# Sensors_TestBoard.net
KiCad netlist of a schematic drawn in Altium Designer
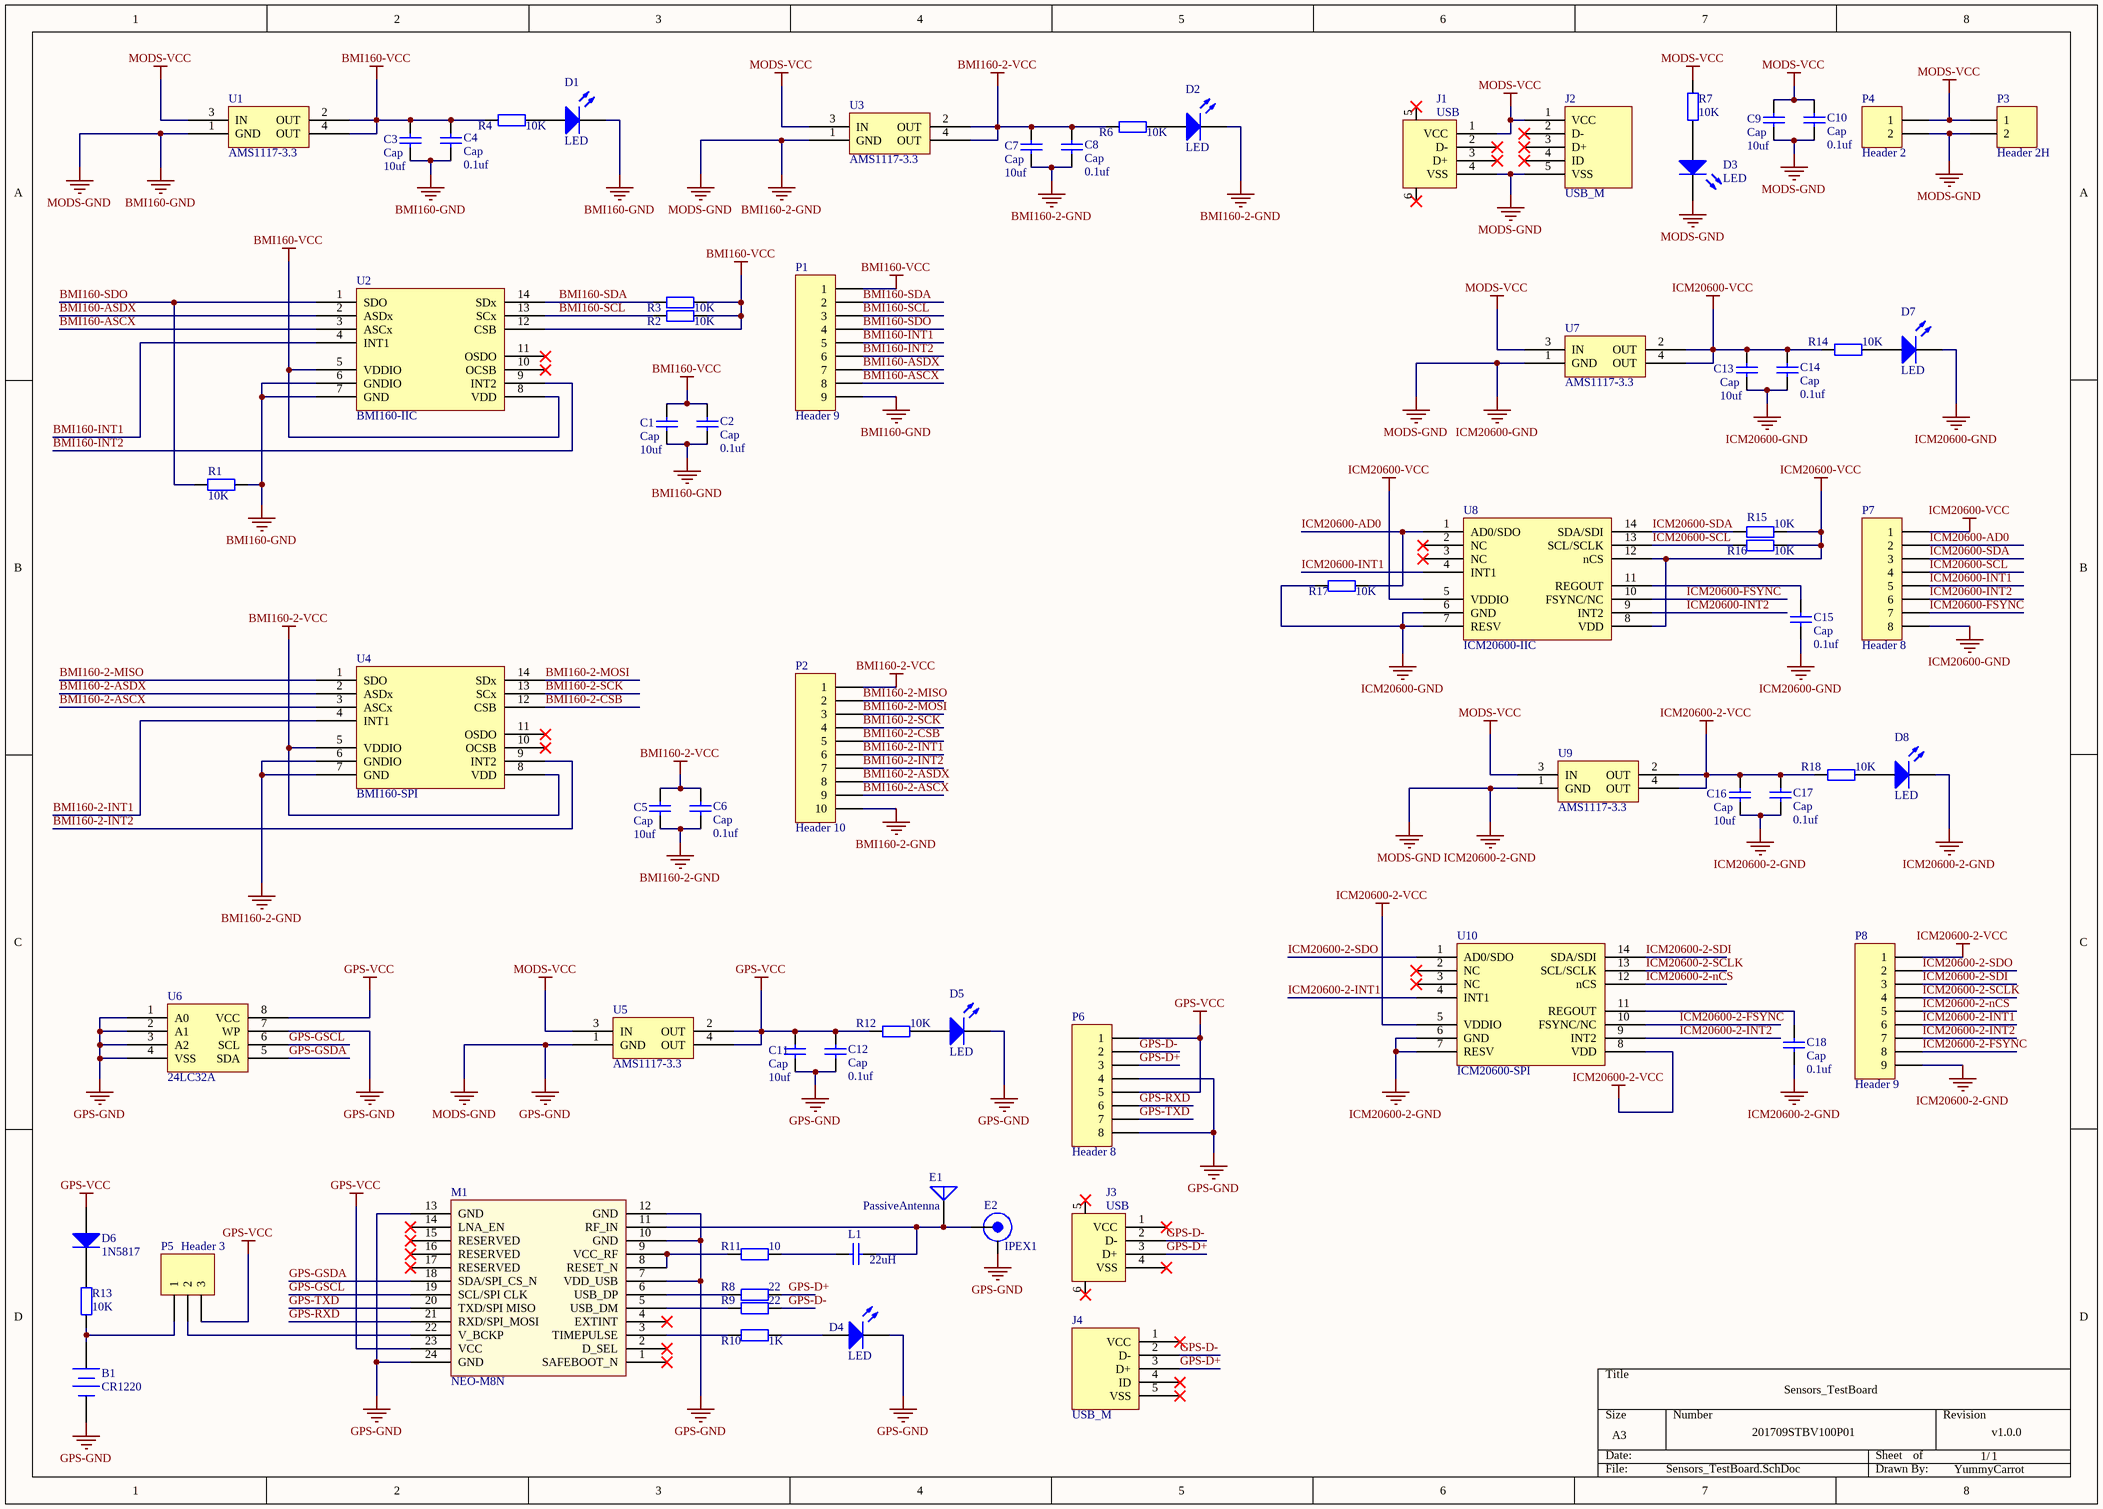
[diagram p0: Sensors_TestBoard.SchDoc]

(export (version "E")
  (design (tool "Eeschema 10.0.6"))
  (components
    (comp (ref "B1") (value "CR1220") (footprint "CR1220") (libsource (lib "Basic_lib") (part "CR1220")))
    (comp (ref "C1")
      (value "Cap")
      (footprint "C1206")
      (fields (field (name "ALTIUM_VALUE") "10uf"))
      (libsource (lib "Basic_lib") (part "Cap"))
    )
    (comp (ref "C2")
      (value "Cap")
      (footprint "C1206")
      (fields (field (name "ALTIUM_VALUE") "0.1uf"))
      (libsource (lib "Basic_lib") (part "Cap"))
    )
    (comp (ref "C3")
      (value "Cap")
      (footprint "C1206")
      (fields (field (name "ALTIUM_VALUE") "10uf"))
      (libsource (lib "Basic_lib") (part "Cap"))
    )
    (comp (ref "C4")
      (value "Cap")
      (footprint "C1206")
      (fields (field (name "ALTIUM_VALUE") "0.1uf"))
      (libsource (lib "Basic_lib") (part "Cap"))
    )
    (comp (ref "C5")
      (value "Cap")
      (footprint "C1206")
      (fields (field (name "ALTIUM_VALUE") "10uf"))
      (libsource (lib "Basic_lib") (part "Cap"))
    )
    (comp (ref "C6")
      (value "Cap")
      (footprint "C1206")
      (fields (field (name "ALTIUM_VALUE") "0.1uf"))
      (libsource (lib "Basic_lib") (part "Cap"))
    )
    (comp (ref "C7")
      (value "Cap")
      (footprint "C1206")
      (fields (field (name "ALTIUM_VALUE") "10uf"))
      (libsource (lib "Basic_lib") (part "Cap"))
    )
    (comp (ref "C8")
      (value "Cap")
      (footprint "C1206")
      (fields (field (name "ALTIUM_VALUE") "0.1uf"))
      (libsource (lib "Basic_lib") (part "Cap"))
    )
    (comp (ref "C9")
      (value "Cap")
      (footprint "C1206")
      (fields (field (name "ALTIUM_VALUE") "10uf"))
      (libsource (lib "Basic_lib") (part "Cap"))
    )
    (comp (ref "C10")
      (value "Cap")
      (footprint "C1206")
      (fields (field (name "ALTIUM_VALUE") "0.1uf"))
      (libsource (lib "Basic_lib") (part "Cap"))
    )
    (comp (ref "C11")
      (value "Cap")
      (footprint "C1206")
      (fields (field (name "ALTIUM_VALUE") "10uf"))
      (libsource (lib "Basic_lib") (part "Cap"))
    )
    (comp (ref "C12")
      (value "Cap")
      (footprint "C1206")
      (fields (field (name "ALTIUM_VALUE") "0.1uf"))
      (libsource (lib "Basic_lib") (part "Cap"))
    )
    (comp (ref "C13")
      (value "Cap")
      (footprint "C1206")
      (fields (field (name "ALTIUM_VALUE") "10uf"))
      (libsource (lib "Basic_lib") (part "Cap"))
    )
    (comp (ref "C14")
      (value "Cap")
      (footprint "C1206")
      (fields (field (name "ALTIUM_VALUE") "0.1uf"))
      (libsource (lib "Basic_lib") (part "Cap"))
    )
    (comp (ref "C15")
      (value "Cap")
      (footprint "C1206")
      (fields (field (name "ALTIUM_VALUE") "0.1uf"))
      (libsource (lib "Basic_lib") (part "Cap"))
    )
    (comp (ref "C16")
      (value "Cap")
      (footprint "C1206")
      (fields (field (name "ALTIUM_VALUE") "10uf"))
      (libsource (lib "Basic_lib") (part "Cap"))
    )
    (comp (ref "C17")
      (value "Cap")
      (footprint "C1206")
      (fields (field (name "ALTIUM_VALUE") "0.1uf"))
      (libsource (lib "Basic_lib") (part "Cap"))
    )
    (comp (ref "C18")
      (value "Cap")
      (footprint "C1206")
      (fields (field (name "ALTIUM_VALUE") "0.1uf"))
      (libsource (lib "Basic_lib") (part "Cap"))
    )
    (comp (ref "D1")
      (value "LED")
      (footprint "3.2X1.6X1.1")
      (description "Typical RED, GREEN, YELLOW, AMBER GaAs LED")
      (fields (field (name "PUBLISHER") "Altium Limited"))
      (libsource (lib "Miscellaneous Devices") (part "LED2"))
    )
    (comp (ref "D2")
      (value "LED")
      (footprint "3.2X1.6X1.1")
      (description "Typical RED, GREEN, YELLOW, AMBER GaAs LED")
      (fields (field (name "PUBLISHER") "Altium Limited"))
      (libsource (lib "Miscellaneous Devices") (part "LED2"))
    )
    (comp (ref "D3")
      (value "LED")
      (footprint "3.2X1.6X1.1")
      (description "Typical RED, GREEN, YELLOW, AMBER GaAs LED")
      (fields (field (name "PUBLISHER") "Altium Limited"))
      (libsource (lib "Miscellaneous Devices") (part "LED2"))
    )
    (comp (ref "D4")
      (value "LED")
      (footprint "3.2X1.6X1.1")
      (description "Typical RED, GREEN, YELLOW, AMBER GaAs LED")
      (fields (field (name "PUBLISHER") "Altium Limited"))
      (libsource (lib "Miscellaneous Devices") (part "LED2"))
    )
    (comp (ref "D5")
      (value "LED")
      (footprint "3.2X1.6X1.1")
      (description "Typical RED, GREEN, YELLOW, AMBER GaAs LED")
      (fields (field (name "PUBLISHER") "Altium Limited"))
      (libsource (lib "Miscellaneous Devices") (part "LED2"))
    )
    (comp (ref "D6")
      (value "1N5817")
      (footprint "Diode-SMA/DO214AC")
      (libsource (lib "Basic_lib") (part "Diode"))
    )
    (comp (ref "D7")
      (value "LED")
      (footprint "3.2X1.6X1.1")
      (description "Typical RED, GREEN, YELLOW, AMBER GaAs LED")
      (fields (field (name "PUBLISHER") "Altium Limited"))
      (libsource (lib "Miscellaneous Devices") (part "LED2"))
    )
    (comp (ref "D8")
      (value "LED")
      (footprint "3.2X1.6X1.1")
      (description "Typical RED, GREEN, YELLOW, AMBER GaAs LED")
      (fields (field (name "PUBLISHER") "Altium Limited"))
      (libsource (lib "Miscellaneous Devices") (part "LED2"))
    )
    (comp (ref "E1")
      (value "PassiveAntenna")
      (footprint "PassiveAntenna25x25")
      (description "无源天线25x25")
      (libsource (lib "Basic_lib") (part "PassiveAntenna"))
    )
    (comp (ref "E2") (value "IPEX1") (footprint "IPEX1") (libsource (lib "Basic_lib") (part "IPEX1")))
    (comp (ref "J1")
      (value "USB")
      (footprint "USB_A1")
      (description "USB接口")
      (libsource (lib "Fszhanglib") (part "USB"))
    )
    (comp (ref "J2")
      (value "USB_M")
      (footprint "USB_MICRO")
      (description "MicroUSB接口")
      (libsource (lib "Fszhanglib") (part "USB_M"))
    )
    (comp (ref "J3")
      (value "USB")
      (footprint "USB_A1")
      (description "USB接口")
      (libsource (lib "Fszhanglib") (part "USB"))
    )
    (comp (ref "J4")
      (value "USB_M")
      (footprint "USB_MICRO")
      (description "MicroUSB接口")
      (libsource (lib "") (part "USB_M_1"))
    )
    (comp (ref "L1")
      (value "22uH")
      (footprint "C1206")
      (fields (field (name "Comment") "Cap"))
      (libsource (lib "Basic_lib") (part "Cap"))
    )
    (comp (ref "M1") (value "NEO-M8N") (footprint "NEO-M8N") (libsource (lib "Sensors_lib") (part "NEO-M8N")))
    (comp (ref "P1")
      (value "Header 9")
      (footprint "HDR1X9")
      (description "Header, 9-Pin")
      (fields (field (name "PUBLISHER") "Altium Limited"))
      (libsource (lib "Miscellaneous Connectors") (part "Header 9"))
    )
    (comp (ref "P2")
      (value "Header 10")
      (footprint "HDR1X10")
      (description "Header, 10-Pin")
      (fields (field (name "PUBLISHER") "Altium Limited"))
      (libsource (lib "Miscellaneous Connectors") (part "Header 10"))
    )
    (comp (ref "P3")
      (value "Header 2H")
      (footprint "HDR1X2H")
      (description "Header, 2-Pin, Right Angle")
      (fields (field (name "PUBLISHER") "Altium Limited"))
      (libsource (lib "Miscellaneous Connectors") (part "Header 2H"))
    )
    (comp (ref "P4")
      (value "Header 2")
      (footprint "HDR1X2")
      (description "Header, 2-Pin")
      (fields (field (name "PUBLISHER") "Altium Limited"))
      (libsource (lib "Miscellaneous Connectors") (part "Header 2"))
    )
    (comp (ref "P5")
      (value "Header 3")
      (footprint "HDR1X3")
      (description "Header, 3-Pin")
      (fields (field (name "PUBLISHER") "Altium Limited"))
      (libsource (lib "Miscellaneous Connectors") (part "Header 3"))
    )
    (comp (ref "P6")
      (value "Header 8")
      (footprint "HDR1X8")
      (description "Header, 8-Pin")
      (fields (field (name "PUBLISHER") "Altium Limited"))
      (libsource (lib "Miscellaneous Connectors") (part "Header 8"))
    )
    (comp (ref "P7")
      (value "Header 8")
      (footprint "HDR1X8")
      (description "Header, 8-Pin")
      (fields (field (name "PUBLISHER") "Altium Limited"))
      (libsource (lib "Miscellaneous Connectors") (part "Header 8"))
    )
    (comp (ref "P8")
      (value "Header 9")
      (footprint "HDR1X9")
      (description "Header, 9-Pin")
      (fields (field (name "PUBLISHER") "Altium Limited"))
      (libsource (lib "Miscellaneous Connectors") (part "Header 9"))
    )
    (comp (ref "R1")
      (value "10K")
      (footprint "R1206")
      (fields (field (name "Comment") "Res"))
      (libsource (lib "Basic_lib") (part "Res"))
    )
    (comp (ref "R2")
      (value "10K")
      (footprint "R1206")
      (fields (field (name "Comment") "Res"))
      (libsource (lib "Basic_lib") (part "Res"))
    )
    (comp (ref "R3")
      (value "10K")
      (footprint "R1206")
      (fields (field (name "Comment") "Res"))
      (libsource (lib "Basic_lib") (part "Res"))
    )
    (comp (ref "R4")
      (value "10K")
      (footprint "R1206")
      (fields (field (name "Comment") "Res"))
      (libsource (lib "Basic_lib") (part "Res"))
    )
    (comp (ref "R6")
      (value "10K")
      (footprint "R1206")
      (fields (field (name "Comment") "Res"))
      (libsource (lib "Basic_lib") (part "Res"))
    )
    (comp (ref "R7")
      (value "10K")
      (footprint "R1206")
      (fields (field (name "Comment") "Res"))
      (libsource (lib "") (part "Res_1"))
    )
    (comp (ref "R8")
      (value "22")
      (footprint "R1206")
      (fields (field (name "Comment") "Res"))
      (libsource (lib "Basic_lib") (part "Res"))
    )
    (comp (ref "R9")
      (value "22")
      (footprint "R1206")
      (fields (field (name "Comment") "Res"))
      (libsource (lib "Basic_lib") (part "Res"))
    )
    (comp (ref "R10")
      (value "1K")
      (footprint "R1206")
      (fields (field (name "Comment") "Res"))
      (libsource (lib "Basic_lib") (part "Res"))
    )
    (comp (ref "R11")
      (value "10")
      (footprint "R1206")
      (fields (field (name "Comment") "Res"))
      (libsource (lib "Basic_lib") (part "Res"))
    )
    (comp (ref "R12")
      (value "10K")
      (footprint "R1206")
      (fields (field (name "Comment") "Res"))
      (libsource (lib "Basic_lib") (part "Res"))
    )
    (comp (ref "R13")
      (value "10K")
      (footprint "R1206")
      (fields (field (name "Comment") "Res"))
      (libsource (lib "") (part "Res_1"))
    )
    (comp (ref "R14")
      (value "10K")
      (footprint "R1206")
      (fields (field (name "Comment") "Res"))
      (libsource (lib "Basic_lib") (part "Res"))
    )
    (comp (ref "R15")
      (value "10K")
      (footprint "R1206")
      (fields (field (name "Comment") "Res"))
      (libsource (lib "Basic_lib") (part "Res"))
    )
    (comp (ref "R16")
      (value "10K")
      (footprint "R1206")
      (fields (field (name "Comment") "Res"))
      (libsource (lib "Basic_lib") (part "Res"))
    )
    (comp (ref "R17")
      (value "10K")
      (footprint "R1206")
      (fields (field (name "Comment") "Res"))
      (libsource (lib "Basic_lib") (part "Res"))
    )
    (comp (ref "R18")
      (value "10K")
      (footprint "R1206")
      (fields (field (name "Comment") "Res"))
      (libsource (lib "Basic_lib") (part "Res"))
    )
    (comp (ref "U1")
      (value "AMS1117-3.3")
      (footprint "AMS1117")
      (libsource (lib "Basic_lib") (part "AMS1117"))
    )
    (comp (ref "U2")
      (value "BMI160-IIC")
      (footprint "BMI160-LGA14")
      (description "BMI160")
      (libsource (lib "Sensors_lib") (part "BMI160"))
    )
    (comp (ref "U3")
      (value "AMS1117-3.3")
      (footprint "AMS1117")
      (libsource (lib "Basic_lib") (part "AMS1117"))
    )
    (comp (ref "U4")
      (value "BMI160-SPI")
      (footprint "BMI160-LGA14")
      (description "BMI160")
      (libsource (lib "Sensors_lib") (part "BMI160"))
    )
    (comp (ref "U5")
      (value "AMS1117-3.3")
      (footprint "AMS1117")
      (libsource (lib "Basic_lib") (part "AMS1117"))
    )
    (comp (ref "U6")
      (value "24LC32A")
      (footprint "24LC32A-SOIC8-3.90mm")
      (libsource (lib "Basic_lib") (part "24LC32A"))
    )
    (comp (ref "U7")
      (value "AMS1117-3.3")
      (footprint "AMS1117")
      (libsource (lib "Basic_lib") (part "AMS1117"))
    )
    (comp (ref "U8")
      (value "ICM20600-IIC")
      (footprint "ICM20600-LGA14")
      (libsource (lib "Sensors_lib") (part "ICM20600"))
    )
    (comp (ref "U9")
      (value "AMS1117-3.3")
      (footprint "AMS1117")
      (libsource (lib "Basic_lib") (part "AMS1117"))
    )
    (comp (ref "U10")
      (value "ICM20600-SPI")
      (footprint "ICM20600-LGA14")
      (libsource (lib "Sensors_lib") (part "ICM20600"))
    )
  )
  (nets
    (net (code "1") (name "/BMI160-2-ASCX") (class "Default")
      (node (ref "P2") (pin "9") (pinfunction "9_9") (pintype "passive"))
      (node (ref "U4") (pin "3") (pinfunction "ASCx_3") (pintype "passive"))
    )
    (net (code "2") (name "/BMI160-2-ASDX") (class "Default")
      (node (ref "P2") (pin "8") (pinfunction "8_8") (pintype "passive"))
      (node (ref "U4") (pin "2") (pinfunction "ASDx_2") (pintype "passive"))
    )
    (net (code "3") (name "/BMI160-2-CSB") (class "Default")
      (node (ref "P2") (pin "5") (pinfunction "5_5") (pintype "passive"))
      (node (ref "U4") (pin "12") (pinfunction "CSB_12") (pintype "passive"))
    )
    (net (code "4") (name "/BMI160-2-INT1") (class "Default")
      (node (ref "P2") (pin "6") (pinfunction "6_6") (pintype "passive"))
      (node (ref "U4") (pin "4") (pinfunction "INT1_4") (pintype "passive"))
    )
    (net (code "5") (name "/BMI160-2-INT2") (class "Default")
      (node (ref "P2") (pin "7") (pinfunction "7_7") (pintype "passive"))
      (node (ref "U4") (pin "9") (pinfunction "INT2_9") (pintype "passive"))
    )
    (net (code "6") (name "/BMI160-2-MISO") (class "Default")
      (node (ref "P2") (pin "2") (pinfunction "2_2") (pintype "passive"))
      (node (ref "U4") (pin "1") (pinfunction "SDO_1") (pintype "passive"))
    )
    (net (code "7") (name "/BMI160-2-MOSI") (class "Default")
      (node (ref "P2") (pin "3") (pinfunction "3_3") (pintype "passive"))
      (node (ref "U4") (pin "14") (pinfunction "SDx_14") (pintype "passive"))
    )
    (net (code "8") (name "/BMI160-2-SCK") (class "Default")
      (node (ref "P2") (pin "4") (pinfunction "4_4") (pintype "passive"))
      (node (ref "U4") (pin "13") (pinfunction "SCx_13") (pintype "passive"))
    )
    (net (code "9") (name "/BMI160-ASCX") (class "Default")
      (node (ref "P1") (pin "8") (pinfunction "8_8") (pintype "passive"))
      (node (ref "U2") (pin "3") (pinfunction "ASCx_3") (pintype "passive"))
    )
    (net (code "10") (name "/BMI160-ASDX") (class "Default")
      (node (ref "P1") (pin "7") (pinfunction "7_7") (pintype "passive"))
      (node (ref "U2") (pin "2") (pinfunction "ASDx_2") (pintype "passive"))
    )
    (net (code "11") (name "/BMI160-INT1") (class "Default")
      (node (ref "P1") (pin "5") (pinfunction "5_5") (pintype "passive"))
      (node (ref "U2") (pin "4") (pinfunction "INT1_4") (pintype "passive"))
    )
    (net (code "12") (name "/BMI160-INT2") (class "Default")
      (node (ref "P1") (pin "6") (pinfunction "6_6") (pintype "passive"))
      (node (ref "U2") (pin "9") (pinfunction "INT2_9") (pintype "passive"))
    )
    (net (code "13") (name "/BMI160-SCL") (class "Default")
      (node (ref "P1") (pin "3") (pinfunction "3_3") (pintype "passive"))
      (node (ref "R2") (pin "1") (pinfunction "1_1") (pintype "passive"))
      (node (ref "U2") (pin "13") (pinfunction "SCx_13") (pintype "passive"))
    )
    (net (code "14") (name "/BMI160-SDA") (class "Default")
      (node (ref "P1") (pin "2") (pinfunction "2_2") (pintype "passive"))
      (node (ref "R3") (pin "1") (pinfunction "1_1") (pintype "passive"))
      (node (ref "U2") (pin "14") (pinfunction "SDx_14") (pintype "passive"))
    )
    (net (code "15") (name "/BMI160-SDO") (class "Default")
      (node (ref "P1") (pin "4") (pinfunction "4_4") (pintype "passive"))
      (node (ref "R1") (pin "1") (pinfunction "1_1") (pintype "passive"))
      (node (ref "U2") (pin "1") (pinfunction "SDO_1") (pintype "passive"))
    )
    (net (code "16") (name "/GPS-D+") (class "Default")
      (node (ref "J3") (pin "3") (pinfunction "D+_3") (pintype "passive"))
      (node (ref "J4") (pin "3") (pinfunction "D+_3") (pintype "passive"))
      (node (ref "P6") (pin "3") (pinfunction "3_3") (pintype "passive"))
      (node (ref "R8") (pin "2") (pinfunction "2_2") (pintype "passive"))
    )
    (net (code "17") (name "/GPS-D-") (class "Default")
      (node (ref "J3") (pin "2") (pinfunction "D-_2") (pintype "passive"))
      (node (ref "J4") (pin "2") (pinfunction "D-_2") (pintype "passive"))
      (node (ref "P6") (pin "2") (pinfunction "2_2") (pintype "passive"))
      (node (ref "R9") (pin "2") (pinfunction "2_2") (pintype "passive"))
    )
    (net (code "18") (name "/GPS-GSCL") (class "Default")
      (node (ref "M1") (pin "19") (pinfunction "SCL/SPI_CLK_19") (pintype "passive"))
      (node (ref "U6") (pin "6") (pinfunction "SCL_6") (pintype "passive"))
    )
    (net (code "19") (name "/GPS-GSDA") (class "Default")
      (node (ref "M1") (pin "18") (pinfunction "SDA/SPI_CS_N_18") (pintype "passive"))
      (node (ref "U6") (pin "5") (pinfunction "SDA_5") (pintype "passive"))
    )
    (net (code "20") (name "/GPS-RXD") (class "Default")
      (node (ref "M1") (pin "21") (pinfunction "RXD/SPI_MOSI_21") (pintype "passive"))
      (node (ref "P6") (pin "6") (pinfunction "6_6") (pintype "passive"))
    )
    (net (code "21") (name "/GPS-TXD") (class "Default")
      (node (ref "M1") (pin "20") (pinfunction "TXD/SPI_MISO_20") (pintype "passive"))
      (node (ref "P6") (pin "7") (pinfunction "7_7") (pintype "passive"))
    )
    (net (code "22") (name "/ICM20600-2-FSYNC") (class "Default")
      (node (ref "P8") (pin "8") (pinfunction "8_8") (pintype "passive"))
      (node (ref "U10") (pin "10") (pinfunction "FSYNC/NC_10") (pintype "passive"))
    )
    (net (code "23") (name "/ICM20600-2-INT1") (class "Default")
      (node (ref "P8") (pin "6") (pinfunction "6_6") (pintype "passive"))
      (node (ref "U10") (pin "4") (pinfunction "INT1_4") (pintype "passive"))
    )
    (net (code "24") (name "/ICM20600-2-INT2") (class "Default")
      (node (ref "P8") (pin "7") (pinfunction "7_7") (pintype "passive"))
      (node (ref "U10") (pin "9") (pinfunction "INT2_9") (pintype "passive"))
    )
    (net (code "25") (name "/ICM20600-2-SCLK") (class "Default")
      (node (ref "P8") (pin "4") (pinfunction "4_4") (pintype "passive"))
      (node (ref "U10") (pin "13") (pinfunction "SCL/SCLK_13") (pintype "passive"))
    )
    (net (code "26") (name "/ICM20600-2-SDI") (class "Default")
      (node (ref "P8") (pin "3") (pinfunction "3_3") (pintype "passive"))
      (node (ref "U10") (pin "14") (pinfunction "SDA/SDI_14") (pintype "passive"))
    )
    (net (code "27") (name "/ICM20600-2-SDO") (class "Default")
      (node (ref "P8") (pin "2") (pinfunction "2_2") (pintype "passive"))
      (node (ref "U10") (pin "1") (pinfunction "AD0/SDO_1") (pintype "passive"))
    )
    (net (code "28") (name "/ICM20600-2-nCS") (class "Default")
      (node (ref "P8") (pin "5") (pinfunction "5_5") (pintype "passive"))
      (node (ref "U10") (pin "12") (pinfunction "nCS_12") (pintype "passive"))
    )
    (net (code "29") (name "/ICM20600-AD0") (class "Default")
      (node (ref "P7") (pin "2") (pinfunction "2_2") (pintype "passive"))
      (node (ref "R17") (pin "2") (pinfunction "2_2") (pintype "passive"))
      (node (ref "U8") (pin "1") (pinfunction "AD0/SDO_1") (pintype "passive"))
    )
    (net (code "30") (name "/ICM20600-FSYNC") (class "Default")
      (node (ref "P7") (pin "7") (pinfunction "7_7") (pintype "passive"))
      (node (ref "U8") (pin "10") (pinfunction "FSYNC/NC_10") (pintype "passive"))
    )
    (net (code "31") (name "/ICM20600-INT1") (class "Default")
      (node (ref "P7") (pin "5") (pinfunction "5_5") (pintype "passive"))
      (node (ref "U8") (pin "4") (pinfunction "INT1_4") (pintype "passive"))
    )
    (net (code "32") (name "/ICM20600-INT2") (class "Default")
      (node (ref "P7") (pin "6") (pinfunction "6_6") (pintype "passive"))
      (node (ref "U8") (pin "9") (pinfunction "INT2_9") (pintype "passive"))
    )
    (net (code "33") (name "/ICM20600-SCL") (class "Default")
      (node (ref "P7") (pin "4") (pinfunction "4_4") (pintype "passive"))
      (node (ref "R16") (pin "1") (pinfunction "1_1") (pintype "passive"))
      (node (ref "U8") (pin "13") (pinfunction "SCL/SCLK_13") (pintype "passive"))
    )
    (net (code "34") (name "/ICM20600-SDA") (class "Default")
      (node (ref "P7") (pin "3") (pinfunction "3_3") (pintype "passive"))
      (node (ref "R15") (pin "1") (pinfunction "1_1") (pintype "passive"))
      (node (ref "U8") (pin "14") (pinfunction "SDA/SDI_14") (pintype "passive"))
    )
    (net (code "35") (name "BMI160-2-GND") (class "Default")
      (node (ref "B1") (pin "2") (pinfunction "-_2") (pintype "passive"))
      (node (ref "C1") (pin "2") (pinfunction "2_2") (pintype "passive"))
      (node (ref "C10") (pin "2") (pinfunction "2_2") (pintype "passive"))
      (node (ref "C11") (pin "2") (pinfunction "2_2") (pintype "passive"))
      (node (ref "C12") (pin "2") (pinfunction "2_2") (pintype "passive"))
      (node (ref "C13") (pin "2") (pinfunction "2_2") (pintype "passive"))
      (node (ref "C14") (pin "2") (pinfunction "2_2") (pintype "passive"))
      (node (ref "C15") (pin "2") (pinfunction "2_2") (pintype "passive"))
      (node (ref "C16") (pin "2") (pinfunction "2_2") (pintype "passive"))
      (node (ref "C17") (pin "2") (pinfunction "2_2") (pintype "passive"))
      (node (ref "C18") (pin "2") (pinfunction "2_2") (pintype "passive"))
      (node (ref "C2") (pin "2") (pinfunction "2_2") (pintype "passive"))
      (node (ref "C3") (pin "2") (pinfunction "2_2") (pintype "passive"))
      (node (ref "C4") (pin "2") (pinfunction "2_2") (pintype "passive"))
      (node (ref "C5") (pin "2") (pinfunction "2_2") (pintype "passive"))
      (node (ref "C6") (pin "2") (pinfunction "2_2") (pintype "passive"))
      (node (ref "C7") (pin "2") (pinfunction "2_2") (pintype "passive"))
      (node (ref "C8") (pin "2") (pinfunction "2_2") (pintype "passive"))
      (node (ref "C9") (pin "2") (pinfunction "2_2") (pintype "passive"))
      (node (ref "D1") (pin "2") (pinfunction "K_2") (pintype "passive"))
      (node (ref "D2") (pin "2") (pinfunction "K_2") (pintype "passive"))
      (node (ref "D3") (pin "2") (pinfunction "K_2") (pintype "passive"))
      (node (ref "D4") (pin "2") (pinfunction "K_2") (pintype "passive"))
      (node (ref "D5") (pin "2") (pinfunction "K_2") (pintype "passive"))
      (node (ref "D7") (pin "2") (pinfunction "K_2") (pintype "passive"))
      (node (ref "D8") (pin "2") (pinfunction "K_2") (pintype "passive"))
      (node (ref "E2") (pin "2") (pinfunction "GND_2") (pintype "passive"))
      (node (ref "J1") (pin "4") (pinfunction "VSS_4") (pintype "passive"))
      (node (ref "J2") (pin "5") (pinfunction "VSS_5") (pintype "passive"))
      (node (ref "M1") (pin "10") (pinfunction "GND_10") (pintype "passive"))
      (node (ref "M1") (pin "12") (pinfunction "GND_12") (pintype "passive"))
      (node (ref "M1") (pin "13") (pinfunction "GND_13") (pintype "passive"))
      (node (ref "M1") (pin "24") (pinfunction "GND_24") (pintype "passive"))
      (node (ref "M1") (pin "7") (pinfunction "VDD_USB_7") (pintype "passive"))
      (node (ref "P1") (pin "9") (pinfunction "9_9") (pintype "passive"))
      (node (ref "P2") (pin "10") (pinfunction "10_10") (pintype "passive"))
      (node (ref "P3") (pin "2") (pinfunction "2_2") (pintype "passive"))
      (node (ref "P4") (pin "2") (pinfunction "2_2") (pintype "passive"))
      (node (ref "P6") (pin "4") (pinfunction "4_4") (pintype "passive"))
      (node (ref "P6") (pin "8") (pinfunction "8_8") (pintype "passive"))
      (node (ref "P7") (pin "8") (pinfunction "8_8") (pintype "passive"))
      (node (ref "P8") (pin "9") (pinfunction "9_9") (pintype "passive"))
      (node (ref "R1") (pin "2") (pinfunction "2_2") (pintype "passive"))
      (node (ref "R17") (pin "1") (pinfunction "1_1") (pintype "passive"))
      (node (ref "U1") (pin "1") (pinfunction "GND_1") (pintype "passive"))
      (node (ref "U10") (pin "6") (pinfunction "GND_6") (pintype "passive"))
      (node (ref "U10") (pin "7") (pinfunction "RESV_7") (pintype "passive"))
      (node (ref "U2") (pin "6") (pinfunction "GNDIO_6") (pintype "passive"))
      (node (ref "U2") (pin "7") (pinfunction "GND_7") (pintype "passive"))
      (node (ref "U3") (pin "1") (pinfunction "GND_1") (pintype "passive"))
      (node (ref "U4") (pin "6") (pinfunction "GNDIO_6") (pintype "passive"))
      (node (ref "U4") (pin "7") (pinfunction "GND_7") (pintype "passive"))
      (node (ref "U5") (pin "1") (pinfunction "GND_1") (pintype "passive"))
      (node (ref "U6") (pin "1") (pinfunction "A0_1") (pintype "passive"))
      (node (ref "U6") (pin "2") (pinfunction "A1_2") (pintype "passive"))
      (node (ref "U6") (pin "3") (pinfunction "A2_3") (pintype "passive"))
      (node (ref "U6") (pin "4") (pinfunction "VSS_4") (pintype "passive"))
      (node (ref "U6") (pin "7") (pinfunction "WP_7") (pintype "passive"))
      (node (ref "U7") (pin "1") (pinfunction "GND_1") (pintype "passive"))
      (node (ref "U8") (pin "6") (pinfunction "GND_6") (pintype "passive"))
      (node (ref "U8") (pin "7") (pinfunction "RESV_7") (pintype "passive"))
      (node (ref "U9") (pin "1") (pinfunction "GND_1") (pintype "passive"))
    )
    (net (code "36") (name "BMI160-2-VCC") (class "Default")
      (node (ref "C5") (pin "1") (pinfunction "1_1") (pintype "passive"))
      (node (ref "C6") (pin "1") (pinfunction "1_1") (pintype "passive"))
      (node (ref "C7") (pin "1") (pinfunction "1_1") (pintype "passive"))
      (node (ref "C8") (pin "1") (pinfunction "1_1") (pintype "passive"))
      (node (ref "P2") (pin "1") (pinfunction "1_1") (pintype "passive"))
      (node (ref "R6") (pin "1") (pinfunction "1_1") (pintype "passive"))
      (node (ref "U3") (pin "2") (pinfunction "OUT_2") (pintype "passive"))
      (node (ref "U3") (pin "4") (pinfunction "OUT_4") (pintype "passive"))
      (node (ref "U4") (pin "5") (pinfunction "VDDIO_5") (pintype "passive"))
      (node (ref "U4") (pin "8") (pinfunction "VDD_8") (pintype "passive"))
    )
    (net (code "37") (name "BMI160-VCC") (class "Default")
      (node (ref "C1") (pin "1") (pinfunction "1_1") (pintype "passive"))
      (node (ref "C2") (pin "1") (pinfunction "1_1") (pintype "passive"))
      (node (ref "C3") (pin "1") (pinfunction "1_1") (pintype "passive"))
      (node (ref "C4") (pin "1") (pinfunction "1_1") (pintype "passive"))
      (node (ref "P1") (pin "1") (pinfunction "1_1") (pintype "passive"))
      (node (ref "R2") (pin "2") (pinfunction "2_2") (pintype "passive"))
      (node (ref "R3") (pin "2") (pinfunction "2_2") (pintype "passive"))
      (node (ref "R4") (pin "1") (pinfunction "1_1") (pintype "passive"))
      (node (ref "U1") (pin "2") (pinfunction "OUT_2") (pintype "passive"))
      (node (ref "U1") (pin "4") (pinfunction "OUT_4") (pintype "passive"))
      (node (ref "U2") (pin "12") (pinfunction "CSB_12") (pintype "passive"))
      (node (ref "U2") (pin "5") (pinfunction "VDDIO_5") (pintype "passive"))
      (node (ref "U2") (pin "8") (pinfunction "VDD_8") (pintype "passive"))
    )
    (net (code "38") (name "GPS-VCC") (class "Default")
      (node (ref "C11") (pin "1") (pinfunction "1_1") (pintype "passive"))
      (node (ref "C12") (pin "1") (pinfunction "1_1") (pintype "passive"))
      (node (ref "D6") (pin "1") (pinfunction "in_1") (pintype "passive"))
      (node (ref "M1") (pin "23") (pinfunction "VCC_23") (pintype "passive"))
      (node (ref "P5") (pin "3") (pinfunction "3_3") (pintype "passive"))
      (node (ref "P6") (pin "1") (pinfunction "1_1") (pintype "passive"))
      (node (ref "P6") (pin "5") (pinfunction "5_5") (pintype "passive"))
      (node (ref "R12") (pin "1") (pinfunction "1_1") (pintype "passive"))
      (node (ref "U5") (pin "2") (pinfunction "OUT_2") (pintype "passive"))
      (node (ref "U5") (pin "4") (pinfunction "OUT_4") (pintype "passive"))
      (node (ref "U6") (pin "8") (pinfunction "VCC_8") (pintype "passive"))
    )
    (net (code "39") (name "ICM20600-2-VCC") (class "Default")
      (node (ref "C16") (pin "1") (pinfunction "1_1") (pintype "passive"))
      (node (ref "C17") (pin "1") (pinfunction "1_1") (pintype "passive"))
      (node (ref "P8") (pin "1") (pinfunction "1_1") (pintype "passive"))
      (node (ref "R18") (pin "1") (pinfunction "1_1") (pintype "passive"))
      (node (ref "U10") (pin "5") (pinfunction "VDDIO_5") (pintype "passive"))
      (node (ref "U10") (pin "8") (pinfunction "VDD_8") (pintype "passive"))
      (node (ref "U9") (pin "2") (pinfunction "OUT_2") (pintype "passive"))
      (node (ref "U9") (pin "4") (pinfunction "OUT_4") (pintype "passive"))
    )
    (net (code "40") (name "ICM20600-VCC") (class "Default")
      (node (ref "C13") (pin "1") (pinfunction "1_1") (pintype "passive"))
      (node (ref "C14") (pin "1") (pinfunction "1_1") (pintype "passive"))
      (node (ref "P7") (pin "1") (pinfunction "1_1") (pintype "passive"))
      (node (ref "R14") (pin "1") (pinfunction "1_1") (pintype "passive"))
      (node (ref "R15") (pin "2") (pinfunction "2_2") (pintype "passive"))
      (node (ref "R16") (pin "2") (pinfunction "2_2") (pintype "passive"))
      (node (ref "U7") (pin "2") (pinfunction "OUT_2") (pintype "passive"))
      (node (ref "U7") (pin "4") (pinfunction "OUT_4") (pintype "passive"))
      (node (ref "U8") (pin "12") (pinfunction "nCS_12") (pintype "passive"))
      (node (ref "U8") (pin "5") (pinfunction "VDDIO_5") (pintype "passive"))
      (node (ref "U8") (pin "8") (pinfunction "VDD_8") (pintype "passive"))
    )
    (net (code "41") (name "MODS-VCC") (class "Default")
      (node (ref "C10") (pin "1") (pinfunction "1_1") (pintype "passive"))
      (node (ref "C9") (pin "1") (pinfunction "1_1") (pintype "passive"))
      (node (ref "J1") (pin "1") (pinfunction "VCC_1") (pintype "passive"))
      (node (ref "J2") (pin "1") (pinfunction "VCC_1") (pintype "passive"))
      (node (ref "P3") (pin "1") (pinfunction "1_1") (pintype "passive"))
      (node (ref "P4") (pin "1") (pinfunction "1_1") (pintype "passive"))
      (node (ref "R7") (pin "1") (pinfunction "1_1") (pintype "passive"))
      (node (ref "U1") (pin "3") (pinfunction "IN_3") (pintype "passive"))
      (node (ref "U3") (pin "3") (pinfunction "IN_3") (pintype "passive"))
      (node (ref "U5") (pin "3") (pinfunction "IN_3") (pintype "passive"))
      (node (ref "U7") (pin "3") (pinfunction "IN_3") (pintype "passive"))
      (node (ref "U9") (pin "3") (pinfunction "IN_3") (pintype "passive"))
    )
    (net (code "42") (name "Net-(B1-+)") (class "Default")
      (node (ref "B1") (pin "1") (pinfunction "+_1") (pintype "passive"))
      (node (ref "P5") (pin "1") (pinfunction "1_1") (pintype "passive"))
      (node (ref "R13") (pin "2") (pinfunction "2_2") (pintype "passive"))
    )
    (net (code "43") (name "Net-(D1-A)") (class "Default")
      (node (ref "D1") (pin "1") (pinfunction "A_1") (pintype "passive"))
      (node (ref "R4") (pin "2") (pinfunction "2_2") (pintype "passive"))
    )
    (net (code "44") (name "Net-(D2-A)") (class "Default")
      (node (ref "D2") (pin "1") (pinfunction "A_1") (pintype "passive"))
      (node (ref "R6") (pin "2") (pinfunction "2_2") (pintype "passive"))
    )
    (net (code "45") (name "Net-(D3-A)") (class "Default")
      (node (ref "D3") (pin "1") (pinfunction "A_1") (pintype "passive"))
      (node (ref "R7") (pin "2") (pinfunction "2_2") (pintype "passive"))
    )
    (net (code "46") (name "Net-(D4-A)") (class "Default")
      (node (ref "D4") (pin "1") (pinfunction "A_1") (pintype "passive"))
      (node (ref "R10") (pin "2") (pinfunction "2_2") (pintype "passive"))
    )
    (net (code "47") (name "Net-(D5-A)") (class "Default")
      (node (ref "D5") (pin "1") (pinfunction "A_1") (pintype "passive"))
      (node (ref "R12") (pin "2") (pinfunction "2_2") (pintype "passive"))
    )
    (net (code "48") (name "Net-(D6-out)") (class "Default")
      (node (ref "D6") (pin "2") (pinfunction "out_2") (pintype "passive"))
      (node (ref "R13") (pin "1") (pinfunction "1_1") (pintype "passive"))
    )
    (net (code "49") (name "Net-(D7-A)") (class "Default")
      (node (ref "D7") (pin "1") (pinfunction "A_1") (pintype "passive"))
      (node (ref "R14") (pin "2") (pinfunction "2_2") (pintype "passive"))
    )
    (net (code "50") (name "Net-(D8-A)") (class "Default")
      (node (ref "D8") (pin "1") (pinfunction "A_1") (pintype "passive"))
      (node (ref "R18") (pin "2") (pinfunction "2_2") (pintype "passive"))
    )
    (net (code "51") (name "Net-(E2-ANT)") (class "Default")
      (node (ref "E1") (pin "1") (pinfunction "1_1") (pintype "passive"))
      (node (ref "E2") (pin "1") (pinfunction "ANT_1") (pintype "passive"))
      (node (ref "L1") (pin "2") (pinfunction "2_2") (pintype "passive"))
      (node (ref "M1") (pin "11") (pinfunction "RF_IN_11") (pintype "passive"))
    )
    (net (code "52") (name "Net-(L1-Pad1)") (class "Default")
      (node (ref "L1") (pin "1") (pinfunction "1_1") (pintype "passive"))
      (node (ref "R11") (pin "2") (pinfunction "2_2") (pintype "passive"))
    )
    (net (code "53") (name "Net-(M1-RESET_N)") (class "Default")
      (node (ref "M1") (pin "8") (pinfunction "RESET_N_8") (pintype "passive"))
      (node (ref "M1") (pin "9") (pinfunction "VCC_RF_9") (pintype "passive"))
      (node (ref "R11") (pin "1") (pinfunction "1_1") (pintype "passive"))
    )
    (net (code "54") (name "Net-(M1-TIMEPULSE)") (class "Default")
      (node (ref "M1") (pin "3") (pinfunction "TIMEPULSE_3") (pintype "passive"))
      (node (ref "R10") (pin "1") (pinfunction "1_1") (pintype "passive"))
    )
    (net (code "55") (name "Net-(M1-USB_DM)") (class "Default")
      (node (ref "M1") (pin "5") (pinfunction "USB_DM_5") (pintype "passive"))
      (node (ref "R9") (pin "1") (pinfunction "1_1") (pintype "passive"))
    )
    (net (code "56") (name "Net-(M1-USB_DP)") (class "Default")
      (node (ref "M1") (pin "6") (pinfunction "USB_DP_6") (pintype "passive"))
      (node (ref "R8") (pin "1") (pinfunction "1_1") (pintype "passive"))
    )
    (net (code "57") (name "Net-(M1-V_BCKP)") (class "Default")
      (node (ref "M1") (pin "22") (pinfunction "V_BCKP_22") (pintype "passive"))
      (node (ref "P5") (pin "2") (pinfunction "2_2") (pintype "passive"))
    )
    (net (code "58") (name "Net-(U8-REGOUT)") (class "Default")
      (node (ref "C15") (pin "1") (pinfunction "1_1") (pintype "passive"))
      (node (ref "U8") (pin "11") (pinfunction "REGOUT_11") (pintype "passive"))
    )
    (net (code "59") (name "Net-(U10-REGOUT)") (class "Default")
      (node (ref "C18") (pin "1") (pinfunction "1_1") (pintype "passive"))
      (node (ref "U10") (pin "11") (pinfunction "REGOUT_11") (pintype "passive"))
    )
    (net (code "60") (name "unconnected-(J1-D+-Pad3)") (class "Default")
      (node (ref "J1") (pin "3") (pinfunction "D+_3") (pintype "passive+no_connect"))
    )
    (net (code "61") (name "unconnected-(J1-D--Pad2)") (class "Default")
      (node (ref "J1") (pin "2") (pinfunction "D-_2") (pintype "passive+no_connect"))
    )
    (net (code "62") (name "unconnected-(J1-Pad5)") (class "Default")
      (node (ref "J1") (pin "5") (pinfunction "5_5") (pintype "passive+no_connect"))
    )
    (net (code "63") (name "unconnected-(J1-Pad6)") (class "Default")
      (node (ref "J1") (pin "6") (pinfunction "6_6") (pintype "passive+no_connect"))
    )
    (net (code "64") (name "unconnected-(J2-D+-Pad3)") (class "Default")
      (node (ref "J2") (pin "3") (pinfunction "D+_3") (pintype "passive+no_connect"))
    )
    (net (code "65") (name "unconnected-(J2-D--Pad2)") (class "Default")
      (node (ref "J2") (pin "2") (pinfunction "D-_2") (pintype "passive+no_connect"))
    )
    (net (code "66") (name "unconnected-(J2-ID-Pad4)") (class "Default")
      (node (ref "J2") (pin "4") (pinfunction "ID_4") (pintype "passive+no_connect"))
    )
    (net (code "67") (name "unconnected-(J3-Pad5)") (class "Default")
      (node (ref "J3") (pin "5") (pinfunction "5_5") (pintype "passive+no_connect"))
    )
    (net (code "68") (name "unconnected-(J3-Pad6)") (class "Default")
      (node (ref "J3") (pin "6") (pinfunction "6_6") (pintype "passive+no_connect"))
    )
    (net (code "69") (name "unconnected-(J3-VCC-Pad1)") (class "Default")
      (node (ref "J3") (pin "1") (pinfunction "VCC_1") (pintype "passive+no_connect"))
    )
    (net (code "70") (name "unconnected-(J3-VSS-Pad4)") (class "Default")
      (node (ref "J3") (pin "4") (pinfunction "VSS_4") (pintype "passive+no_connect"))
    )
    (net (code "71") (name "unconnected-(J4-ID-Pad4)") (class "Default")
      (node (ref "J4") (pin "4") (pinfunction "ID_4") (pintype "passive+no_connect"))
    )
    (net (code "72") (name "unconnected-(J4-VCC-Pad1)") (class "Default")
      (node (ref "J4") (pin "1") (pinfunction "VCC_1") (pintype "passive+no_connect"))
    )
    (net (code "73") (name "unconnected-(J4-VSS-Pad5)") (class "Default")
      (node (ref "J4") (pin "5") (pinfunction "VSS_5") (pintype "passive+no_connect"))
    )
    (net (code "74") (name "unconnected-(M1-D_SEL-Pad2)") (class "Default")
      (node (ref "M1") (pin "2") (pinfunction "D_SEL_2") (pintype "passive+no_connect"))
    )
    (net (code "75") (name "unconnected-(M1-EXTINT-Pad4)") (class "Default")
      (node (ref "M1") (pin "4") (pinfunction "EXTINT_4") (pintype "passive+no_connect"))
    )
    (net (code "76") (name "unconnected-(M1-LNA_EN-Pad14)") (class "Default")
      (node (ref "M1") (pin "14") (pinfunction "LNA_EN_14") (pintype "passive+no_connect"))
    )
    (net (code "77") (name "unconnected-(M1-RESERVED-Pad15)") (class "Default")
      (node (ref "M1") (pin "15") (pinfunction "RESERVED_15") (pintype "passive+no_connect"))
    )
    (net (code "78") (name "unconnected-(M1-RESERVED-Pad16)") (class "Default")
      (node (ref "M1") (pin "16") (pinfunction "RESERVED_16") (pintype "passive+no_connect"))
    )
    (net (code "79") (name "unconnected-(M1-RESERVED-Pad17)") (class "Default")
      (node (ref "M1") (pin "17") (pinfunction "RESERVED_17") (pintype "passive+no_connect"))
    )
    (net (code "80") (name "unconnected-(M1-SAFEBOOT_N-Pad1)") (class "Default")
      (node (ref "M1") (pin "1") (pinfunction "SAFEBOOT_N_1") (pintype "passive+no_connect"))
    )
    (net (code "81") (name "unconnected-(U2-OCSB-Pad10)") (class "Default")
      (node (ref "U2") (pin "10") (pinfunction "OCSB_10") (pintype "passive+no_connect"))
    )
    (net (code "82") (name "unconnected-(U2-OSDO-Pad11)") (class "Default")
      (node (ref "U2") (pin "11") (pinfunction "OSDO_11") (pintype "passive+no_connect"))
    )
    (net (code "83") (name "unconnected-(U4-OCSB-Pad10)") (class "Default")
      (node (ref "U4") (pin "10") (pinfunction "OCSB_10") (pintype "passive+no_connect"))
    )
    (net (code "84") (name "unconnected-(U4-OSDO-Pad11)") (class "Default")
      (node (ref "U4") (pin "11") (pinfunction "OSDO_11") (pintype "passive+no_connect"))
    )
    (net (code "85") (name "unconnected-(U8-NC-Pad2)") (class "Default")
      (node (ref "U8") (pin "2") (pinfunction "NC_2") (pintype "passive+no_connect"))
    )
    (net (code "86") (name "unconnected-(U8-NC-Pad3)") (class "Default")
      (node (ref "U8") (pin "3") (pinfunction "NC_3") (pintype "passive+no_connect"))
    )
    (net (code "87") (name "unconnected-(U10-NC-Pad2)") (class "Default")
      (node (ref "U10") (pin "2") (pinfunction "NC_2") (pintype "passive+no_connect"))
    )
    (net (code "88") (name "unconnected-(U10-NC-Pad3)") (class "Default")
      (node (ref "U10") (pin "3") (pinfunction "NC_3") (pintype "passive+no_connect"))
    )
  )
)
